# SCH_BIKE-IOT-PCB-BY-AIM_2024-07-08.net
KiCad netlist of a schematic drawn in EasyEDA
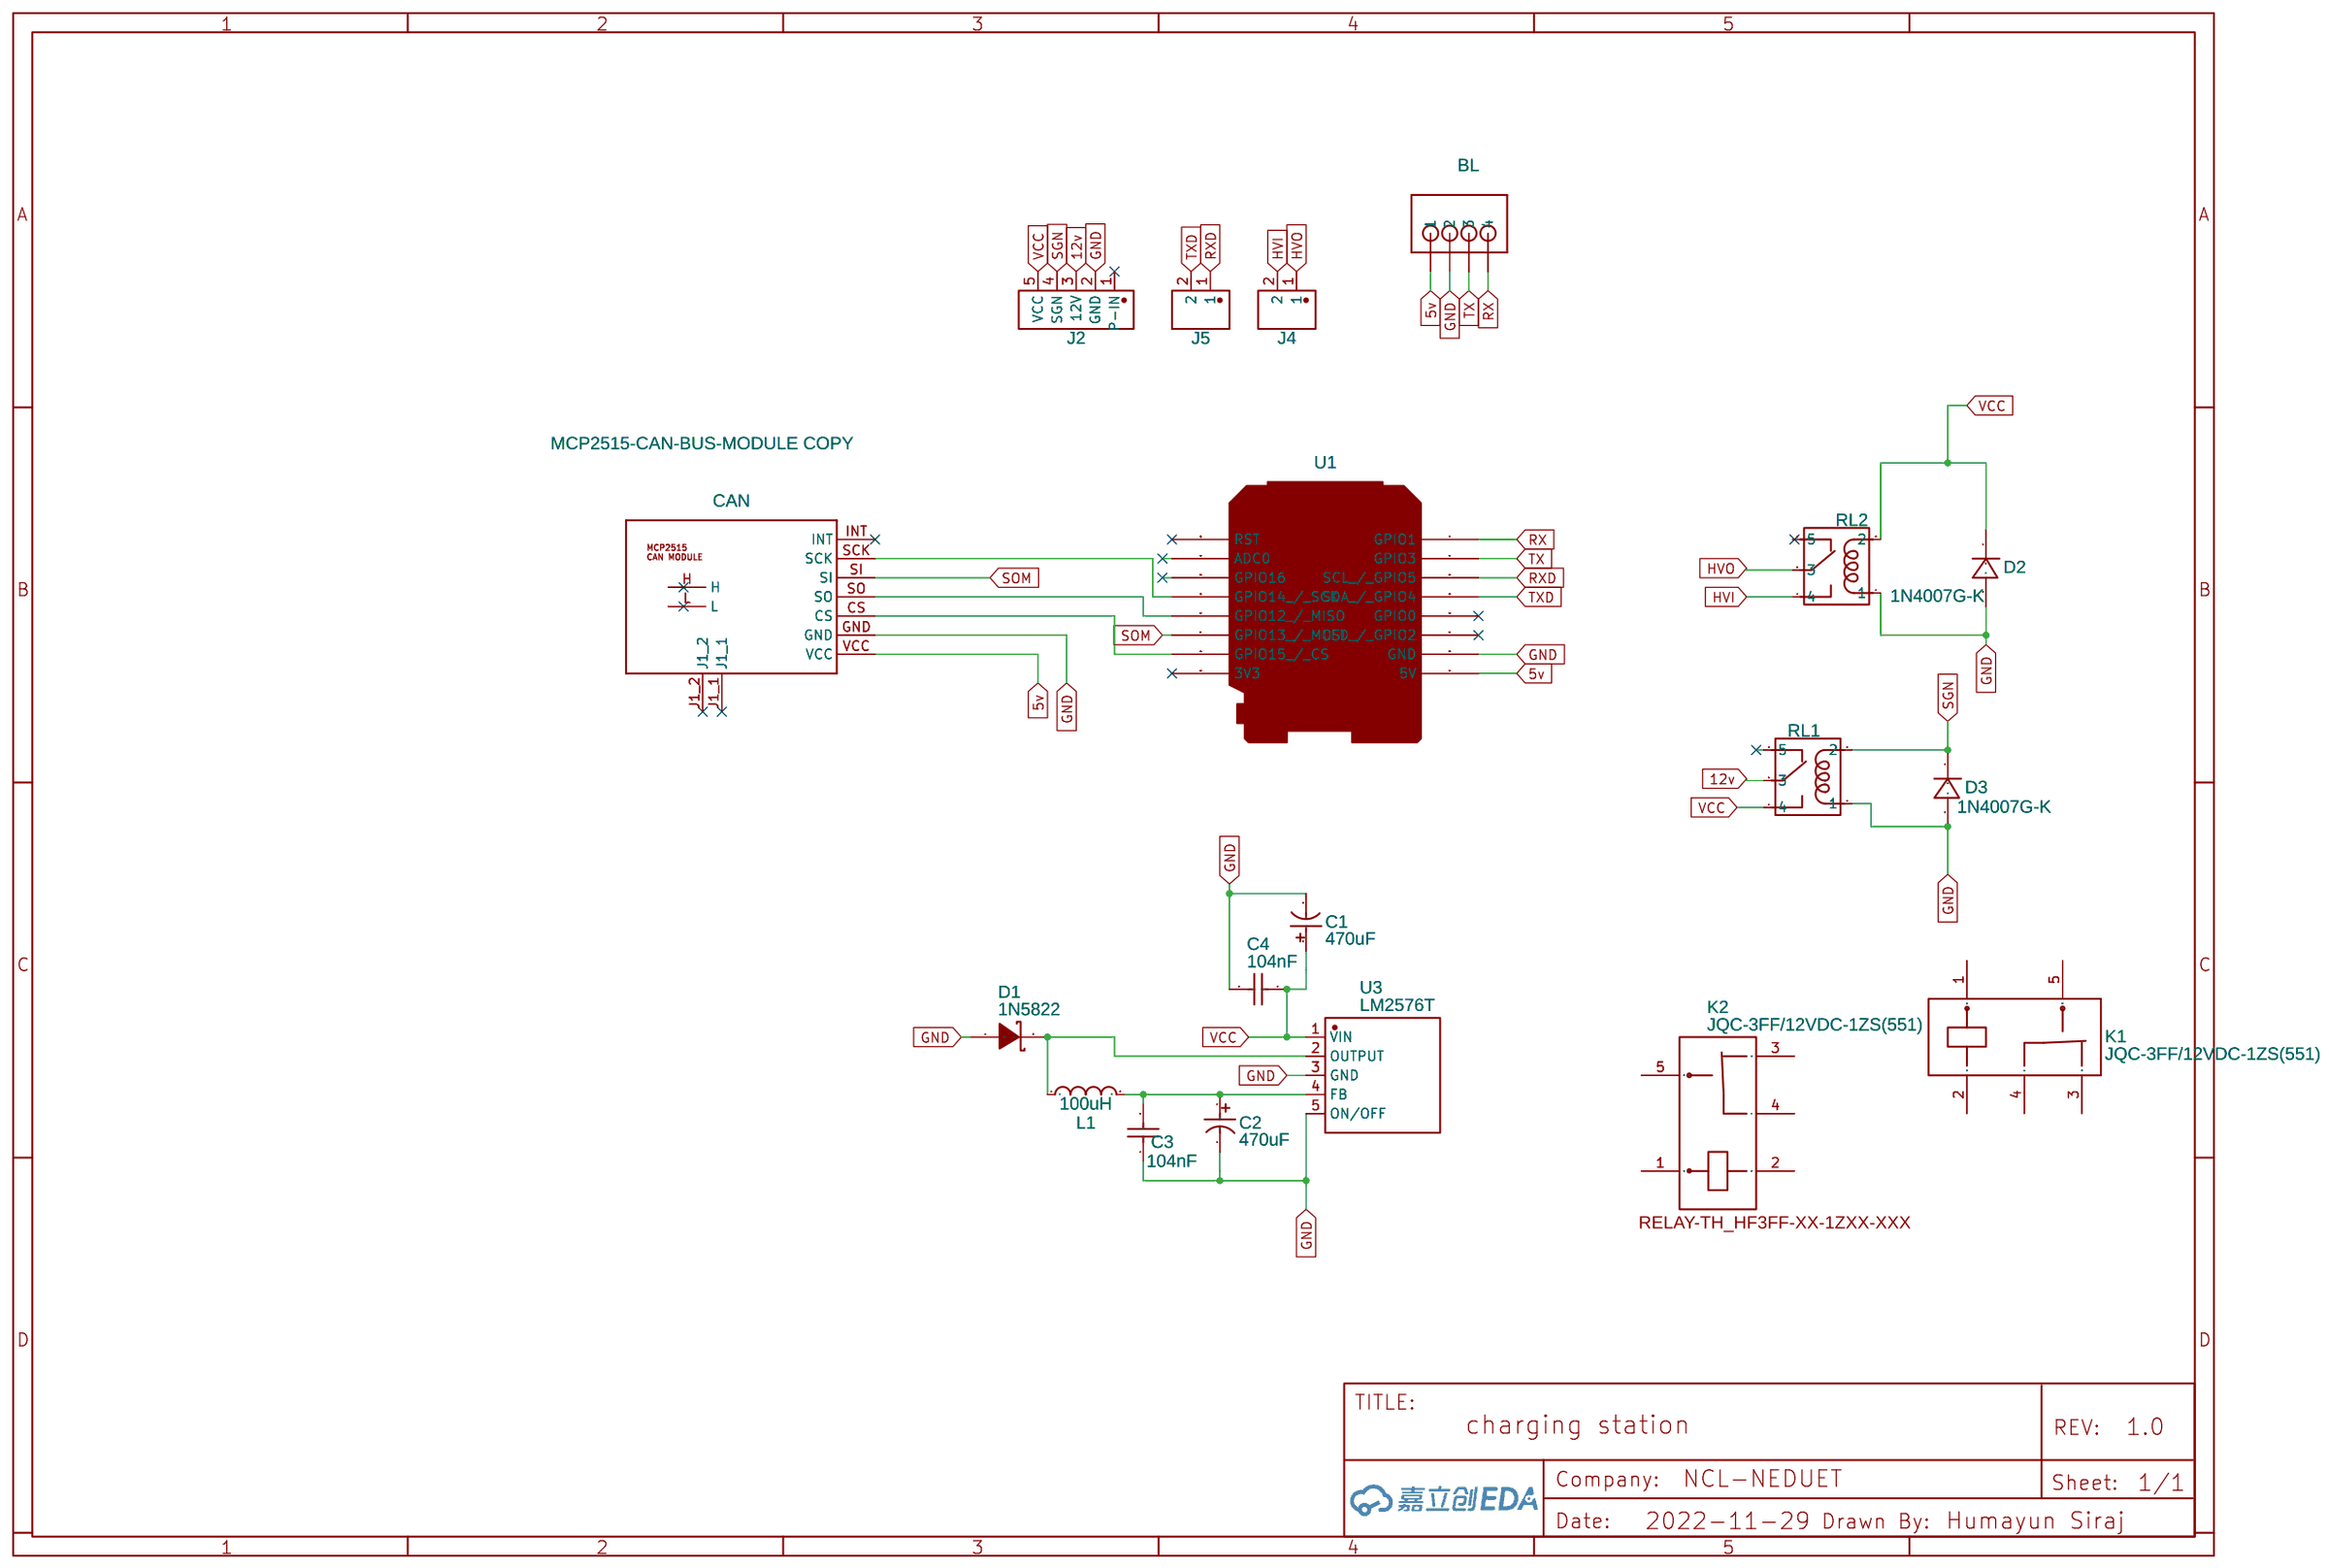
[diagram p0: schematic sheet]

(export (version "E")
  (design (tool "Eeschema 10.0.6"))
  (components
    (comp (ref "BL") (value "JST-PH_4-PIN_HEADER") (libsource (lib "") (part "JST-PH_4-PIN_HEADER")))
    (comp (ref "C1")
      (value "470uF")
      (fields (field (name "Manufacturer Part") "ERS1HM471G20OT") (field (name "Manufacturer") "AISHI(艾华集团)"))
      (libsource (lib "") (part "ERS1HM471G20OT"))
    )
    (comp (ref "C2")
      (value "470uF")
      (fields (field (name "Manufacturer Part") "ERS1HM471G20OT") (field (name "Manufacturer") "AISHI(艾华集团)"))
      (libsource (lib "") (part "ERS1HM471G20OT_1"))
    )
    (comp (ref "C3")
      (value "104nF")
      (fields
        (field (name "Manufacturer Part") "Calibration capacitor100nF（104）100V,5%")
        (field (name "Manufacturer") "ReliaPro")
      )
      (libsource (lib "") (part "Calibration capacitor100nF（104）100V,5%_1"))
    )
    (comp (ref "C4")
      (value "104nF")
      (fields
        (field (name "Manufacturer Part") "Calibration capacitor100nF（104）100V,5%")
        (field (name "Manufacturer") "ReliaPro")
      )
      (libsource (lib "") (part "Calibration capacitor100nF（104）100V,5%"))
    )
    (comp (ref "CAN")
      (value "MCP2515-CAN-BUS-MODULE COPY")
      (libsource (lib "") (part "MCP2515-CAN-BUS-MODULE COPY"))
    )
    (comp (ref "D1")
      (value "1N5822")
      (fields (field (name "Manufacturer") "MDD(辰达半导体)"))
      (libsource (lib "") (part "1N5822"))
    )
    (comp (ref "D2")
      (value "1N4007G-K")
      (fields (field (name "Manufacturer") "Taiwan Semiconductor(台湾半导体)"))
      (libsource (lib "") (part "1N4007G-K"))
    )
    (comp (ref "D3")
      (value "1N4007G-K")
      (fields (field (name "Manufacturer") "Taiwan Semiconductor(台湾半导体)"))
      (libsource (lib "") (part "1N4007G-K"))
    )
    (comp (ref "J2")
      (value "HT396V-3.96-5P")
      (fields (field (name "Manufacturer") "KEFA(科发)"))
      (libsource (lib "") (part "HT396V-3.96-5P"))
    )
    (comp (ref "J4")
      (value "HT396V-3.96-2P_C577788")
      (fields (field (name "Manufacturer Part") "HT396V-3.96-2P") (field (name "Manufacturer") "KEFA(科发)"))
      (libsource (lib "") (part "HT396V-3.96-2P_C577788"))
    )
    (comp (ref "J5")
      (value "HT396V-3.96-2P_C577788")
      (fields (field (name "Manufacturer Part") "HT396V-3.96-2P") (field (name "Manufacturer") "KEFA(科发)"))
      (libsource (lib "") (part "HT396V-3.96-2P_C577788"))
    )
    (comp (ref "K1")
      (value "JQC-3FF/12VDC-1ZS(551)")
      (fields
        (field (name "Manufacturer Part") "JQC-3FF/12VDC-1ZS（551)")
        (field (name "Manufacturer") "HF(宏发)")
      )
      (libsource (lib "") (part "JQC-3FF/12VDC-1ZS(551)_1"))
    )
    (comp (ref "K2")
      (value "JQC-3FF/12VDC-1ZS(551)")
      (fields
        (field (name "Manufacturer Part") "JQC-3FF/12VDC-1ZS（551)")
        (field (name "Manufacturer") "HF(宏发)")
      )
      (libsource (lib "") (part "JQC-3FF/12VDC-1ZS(551)"))
    )
    (comp (ref "L1")
      (value "100uH")
      (fields (field (name "Manufacturer Part") "XR10*16-101K-L") (field (name "Manufacturer") "XR(祥如)"))
      (libsource (lib "") (part "XR10*16-101K-L"))
    )
    (comp (ref "RL1")
      (value "5 Pin Relay")
      (fields (field (name "Manufacturer Part") "JQC-3FF"))
      (libsource (lib "") (part "5 Pin Relay"))
    )
    (comp (ref "RL2")
      (value "5 Pin Relay")
      (fields (field (name "Manufacturer Part") "JQC-3FF"))
      (libsource (lib "") (part "5 Pin Relay"))
    )
    (comp (ref "U1") (value "ESP8266 D1 Mini") (libsource (lib "") (part "ESP8266 D1 Mini")))
    (comp (ref "U3")
      (value "LM2576T")
      (fields
        (field (name "Manufacturer Part") "LM2576T-ADJ")
        (field (name "Manufacturer") "Huaguan Semicon")
      )
      (libsource (lib "") (part "LM2576T"))
    )
  )
  (nets
    (net (code "1") (name "5v") (class "Default")
      (node (ref "BL") (pin "P1") (pinfunction "1_P1") (pintype "unspecified"))
      (node (ref "CAN") (pin "VCC") (pinfunction "VCC_VCC") (pintype "bidirectional"))
      (node (ref "U1") (pin "5V") (pinfunction "5V_5V") (pintype "passive"))
    )
    (net (code "2") (name "12v") (class "Default")
      (node (ref "J2") (pin "3") (pinfunction "12V_3") (pintype "unspecified"))
      (node (ref "RL1") (pin "3") (pinfunction "3_3") (pintype "unspecified"))
    )
    (net (code "3") (name "GND") (class "Default")
      (node (ref "BL") (pin "P2") (pinfunction "2_P2") (pintype "unspecified"))
      (node (ref "C1") (pin "2") (pinfunction "2_2") (pintype "input"))
      (node (ref "C2") (pin "2") (pinfunction "2_2") (pintype "input"))
      (node (ref "C3") (pin "1") (pinfunction "1_1") (pintype "input"))
      (node (ref "C4") (pin "1") (pinfunction "1_1") (pintype "input"))
      (node (ref "CAN") (pin "GND") (pinfunction "GND_GND") (pintype "bidirectional"))
      (node (ref "D1") (pin "1") (pinfunction "A_1") (pintype "unspecified"))
      (node (ref "D2") (pin "2") (pinfunction "A_2") (pintype "unspecified"))
      (node (ref "D3") (pin "2") (pinfunction "A_2") (pintype "unspecified"))
      (node (ref "J2") (pin "2") (pinfunction "GND_2") (pintype "unspecified"))
      (node (ref "RL1") (pin "1") (pinfunction "1_1") (pintype "unspecified"))
      (node (ref "RL2") (pin "1") (pinfunction "1_1") (pintype "unspecified"))
      (node (ref "U1") (pin "GND") (pinfunction "GND_GND") (pintype "passive"))
      (node (ref "U3") (pin "3") (pinfunction "GND_3") (pintype "unspecified"))
      (node (ref "U3") (pin "5") (pinfunction "ON/OFF_5") (pintype "unspecified"))
    )
    (net (code "4") (name "HVI") (class "Default")
      (node (ref "J4") (pin "2") (pinfunction "2_2") (pintype "unspecified"))
      (node (ref "RL2") (pin "4") (pinfunction "4_4") (pintype "unspecified"))
    )
    (net (code "5") (name "HVO") (class "Default")
      (node (ref "J4") (pin "1") (pinfunction "1_1") (pintype "unspecified"))
      (node (ref "RL2") (pin "3") (pinfunction "3_3") (pintype "unspecified"))
    )
    (net (code "6") (name "Net-(D1-K)") (class "Default")
      (node (ref "D1") (pin "2") (pinfunction "K_2") (pintype "unspecified"))
      (node (ref "L1") (pin "1") (pinfunction "1_1") (pintype "unspecified"))
      (node (ref "U3") (pin "2") (pinfunction "OUTPUT_2") (pintype "unspecified"))
    )
    (net (code "7") (name "Net-(U1-GPIO12_{slash}_MISO)") (class "Default")
      (node (ref "CAN") (pin "SO") (pinfunction "SO_SO") (pintype "bidirectional"))
      (node (ref "U1") (pin "D6") (pinfunction "GPIO12_/_MISO_D6") (pintype "bidirectional"))
    )
    (net (code "8") (name "Net-(U1-GPIO14_{slash}_SCK)") (class "Default")
      (node (ref "CAN") (pin "SCK") (pinfunction "SCK_SCK") (pintype "bidirectional"))
      (node (ref "U1") (pin "D5") (pinfunction "GPIO14_/_SCK_D5") (pintype "bidirectional"))
    )
    (net (code "9") (name "Net-(U1-GPIO15_{slash}_CS)") (class "Default")
      (node (ref "CAN") (pin "CS") (pinfunction "CS_CS") (pintype "bidirectional"))
      (node (ref "U1") (pin "D8") (pinfunction "GPIO15_/_CS_D8") (pintype "bidirectional"))
    )
    (net (code "10") (name "Net-(U3-FB)") (class "Default")
      (node (ref "C2") (pin "1") (pinfunction "1_1") (pintype "input"))
      (node (ref "C3") (pin "2") (pinfunction "2_2") (pintype "input"))
      (node (ref "L1") (pin "2") (pinfunction "2_2") (pintype "unspecified"))
      (node (ref "U3") (pin "4") (pinfunction "FB_4") (pintype "unspecified"))
    )
    (net (code "11") (name "RX") (class "Default")
      (node (ref "BL") (pin "P4") (pinfunction "4_P4") (pintype "unspecified"))
      (node (ref "U1") (pin "TX") (pinfunction "GPIO1_TX") (pintype "bidirectional"))
    )
    (net (code "12") (name "RXD") (class "Default")
      (node (ref "J5") (pin "1") (pinfunction "1_1") (pintype "unspecified"))
      (node (ref "U1") (pin "D1") (pinfunction "SCL_/_GPIO5_D1") (pintype "bidirectional"))
    )
    (net (code "13") (name "SGN") (class "Default")
      (node (ref "D3") (pin "1") (pinfunction "C_1") (pintype "unspecified"))
      (node (ref "J2") (pin "4") (pinfunction "SGN_4") (pintype "unspecified"))
      (node (ref "RL1") (pin "2") (pinfunction "2_2") (pintype "unspecified"))
    )
    (net (code "14") (name "SOM") (class "Default")
      (node (ref "CAN") (pin "SI") (pinfunction "SI_SI") (pintype "bidirectional"))
      (node (ref "U1") (pin "D7") (pinfunction "GPIO13_/_MOSI_D7") (pintype "bidirectional"))
    )
    (net (code "15") (name "TX") (class "Default")
      (node (ref "BL") (pin "P3") (pinfunction "3_P3") (pintype "unspecified"))
      (node (ref "U1") (pin "RX") (pinfunction "GPIO3_RX") (pintype "bidirectional"))
    )
    (net (code "16") (name "TXD") (class "Default")
      (node (ref "J5") (pin "2") (pinfunction "2_2") (pintype "unspecified"))
      (node (ref "U1") (pin "D2") (pinfunction "SDA_/_GPIO4_D2") (pintype "bidirectional"))
    )
    (net (code "17") (name "VCC") (class "Default")
      (node (ref "C1") (pin "1") (pinfunction "1_1") (pintype "input"))
      (node (ref "C4") (pin "2") (pinfunction "2_2") (pintype "input"))
      (node (ref "D2") (pin "1") (pinfunction "C_1") (pintype "unspecified"))
      (node (ref "J2") (pin "5") (pinfunction "VCC_5") (pintype "unspecified"))
      (node (ref "RL1") (pin "4") (pinfunction "4_4") (pintype "unspecified"))
      (node (ref "RL2") (pin "2") (pinfunction "2_2") (pintype "unspecified"))
      (node (ref "U3") (pin "1") (pinfunction "VIN_1") (pintype "unspecified"))
    )
    (net (code "18") (name "unconnected-(CAN-PadH)") (class "Default")
      (node (ref "CAN") (pin "H") (pinfunction "H_H") (pintype "bidirectional+no_connect"))
    )
    (net (code "19") (name "unconnected-(CAN-PadINT)") (class "Default")
      (node (ref "CAN") (pin "INT") (pinfunction "INT_INT") (pintype "bidirectional+no_connect"))
    )
    (net (code "20") (name "unconnected-(CAN-PadJ1_1)") (class "Default")
      (node (ref "CAN") (pin "J1_1") (pinfunction "J1_1_J1_1") (pintype "bidirectional+no_connect"))
    )
    (net (code "21") (name "unconnected-(CAN-PadJ1_2)") (class "Default")
      (node (ref "CAN") (pin "J1_2") (pinfunction "J1_2_J1_2") (pintype "bidirectional+no_connect"))
    )
    (net (code "22") (name "unconnected-(CAN-PadL)") (class "Default")
      (node (ref "CAN") (pin "L") (pinfunction "L_L") (pintype "bidirectional+no_connect"))
    )
    (net (code "23") (name "unconnected-(J2-P-IN-Pad1)") (class "Default")
      (node (ref "J2") (pin "1") (pinfunction "P-IN_1") (pintype "unspecified+no_connect"))
    )
    (net (code "24") (name "unconnected-(K1-Pad1)") (class "Default")
      (node (ref "K1") (pin "1") (pinfunction "1_1") (pintype "input"))
    )
    (net (code "25") (name "unconnected-(K1-Pad2)") (class "Default")
      (node (ref "K1") (pin "2") (pinfunction "2_2") (pintype "input"))
    )
    (net (code "26") (name "unconnected-(K1-Pad3)") (class "Default")
      (node (ref "K1") (pin "3") (pinfunction "3_3") (pintype "input"))
    )
    (net (code "27") (name "unconnected-(K1-Pad4)") (class "Default")
      (node (ref "K1") (pin "4") (pinfunction "4_4") (pintype "input"))
    )
    (net (code "28") (name "unconnected-(K1-Pad5)") (class "Default")
      (node (ref "K1") (pin "5") (pinfunction "5_5") (pintype "input"))
    )
    (net (code "29") (name "unconnected-(K2-Pad1)") (class "Default")
      (node (ref "K2") (pin "1") (pinfunction "1_1") (pintype "input"))
    )
    (net (code "30") (name "unconnected-(K2-Pad2)") (class "Default")
      (node (ref "K2") (pin "2") (pinfunction "2_2") (pintype "input"))
    )
    (net (code "31") (name "unconnected-(K2-Pad3)") (class "Default")
      (node (ref "K2") (pin "3") (pinfunction "3_3") (pintype "input"))
    )
    (net (code "32") (name "unconnected-(K2-Pad4)") (class "Default")
      (node (ref "K2") (pin "4") (pinfunction "4_4") (pintype "input"))
    )
    (net (code "33") (name "unconnected-(K2-Pad5)") (class "Default")
      (node (ref "K2") (pin "5") (pinfunction "5_5") (pintype "input"))
    )
    (net (code "34") (name "unconnected-(RL1-Pad5)") (class "Default")
      (node (ref "RL1") (pin "5") (pinfunction "5_5") (pintype "unspecified+no_connect"))
    )
    (net (code "35") (name "unconnected-(RL2-Pad5)") (class "Default")
      (node (ref "RL2") (pin "5") (pinfunction "5_5") (pintype "unspecified"))
    )
    (net (code "36") (name "unconnected-(U1-ADC0-PadA0)") (class "Default")
      (node (ref "U1") (pin "A0") (pinfunction "ADC0_A0") (pintype "input+no_connect"))
    )
    (net (code "37") (name "unconnected-(U1-GPIO0-PadD3)") (class "Default")
      (node (ref "U1") (pin "D3") (pinfunction "GPIO0_D3") (pintype "bidirectional+no_connect"))
    )
    (net (code "38") (name "unconnected-(U1-GPIO16-PadD0)") (class "Default")
      (node (ref "U1") (pin "D0") (pinfunction "GPIO16_D0") (pintype "bidirectional+no_connect"))
    )
    (net (code "39") (name "unconnected-(U1-LED_{slash}_GPIO2-PadD4)") (class "Default")
      (node (ref "U1") (pin "D4") (pinfunction "LED_/_GPIO2_D4") (pintype "bidirectional+no_connect"))
    )
    (net (code "40") (name "unconnected-(U1-Pad3V3)") (class "Default")
      (node (ref "U1") (pin "3V3") (pinfunction "3V3_3V3") (pintype "passive+no_connect"))
    )
    (net (code "41") (name "unconnected-(U1-PadRST)") (class "Default")
      (node (ref "U1") (pin "RST") (pinfunction "RST_RST") (pintype "input+no_connect"))
    )
  )
)
